# Sheet2.net
KiCad netlist of a schematic drawn in Altium Designer
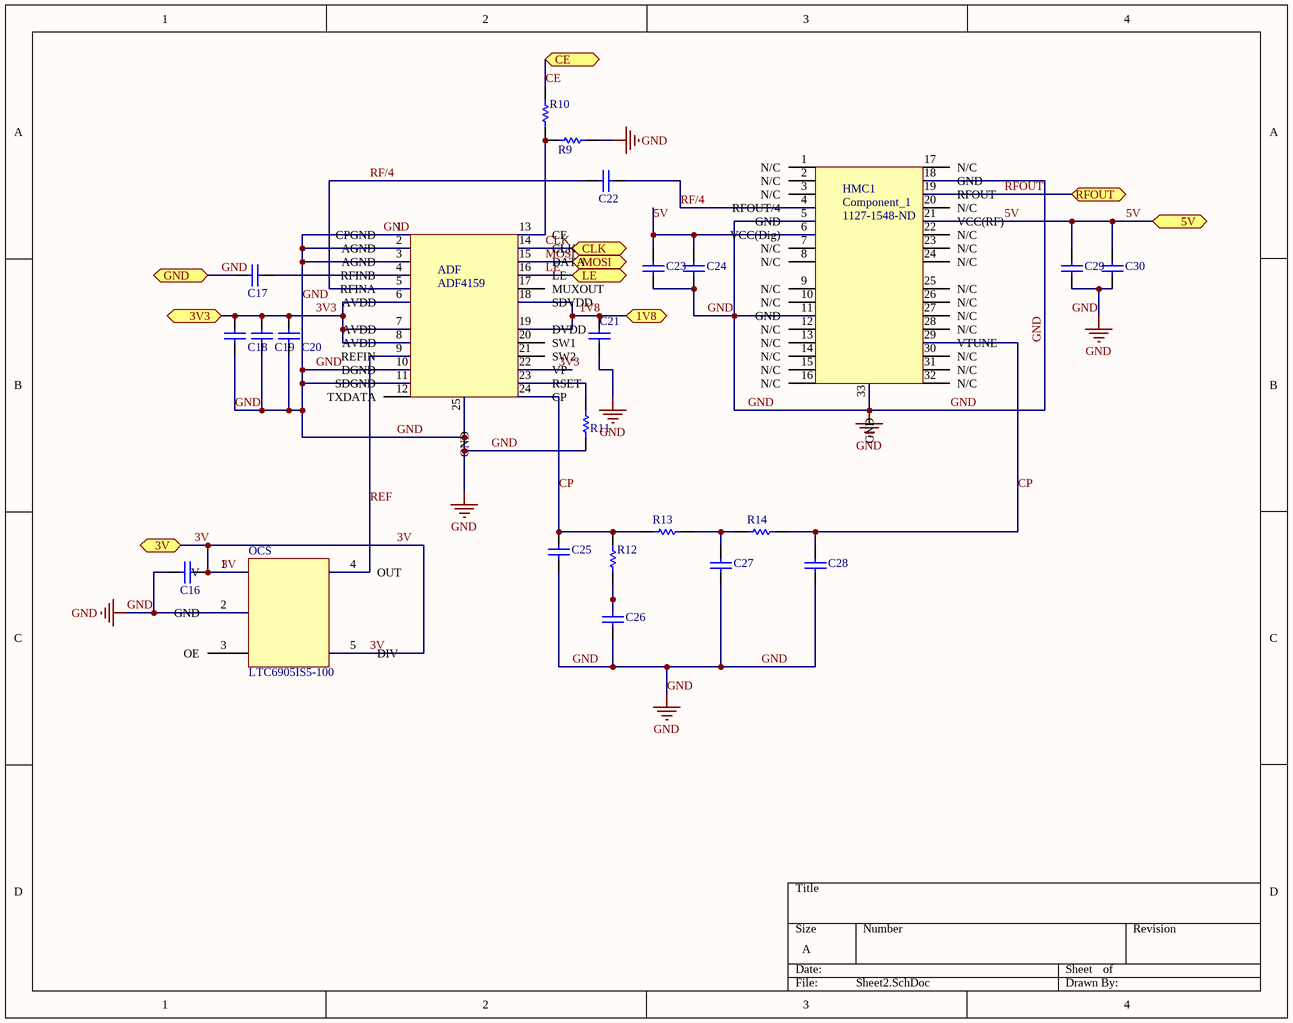
[diagram p0: Sheet2.SchDoc]

(export (version "E")
  (design (tool "Eeschema 10.0.6"))
  (components
    (comp (ref "ADF")
      (value "ADF4159")
      (footprint "QFN50P400X400X80_HS-25N")
      (libsource (lib "ADF4159") (part "ADF4159"))
    )
    (comp (ref "C16")
      (value "CAP 0.1uF 16V 0603(1608)")
      (footprint "CAPC0603(1608)100_L")
      (description "CAP 0.1uF 16V ±1% 0603 (1608 Metric) Thickness 1mm SMD")
      (fields (field (name "TOLERANCE") "Â±1%"))
      (libsource (lib "Altium Content Vault") (part "CMP-1035-01744-1"))
    )
    (comp (ref "C17")
      (value "CAP 100pF 16V 0603(1608)")
      (footprint "CAPC0603(1608)100_L")
      (description "CAP 100pF 16V ±1% 0603 (1608 Metric) Thickness 1mm SMD")
      (fields (field (name "TOLERANCE") "Â±1%"))
      (libsource (lib "Altium Content Vault") (part "CMP-1035-01744-1"))
    )
    (comp (ref "C18")
      (value "CAP 10uF 16V 0603(1608)")
      (footprint "CAPC0603(1608)100_L")
      (description "CAP 10uF 16V ±1% 0603 (1608 Metric) Thickness 1mm SMD")
      (fields (field (name "TOLERANCE") "Â±1%"))
      (libsource (lib "Altium Content Vault") (part "CMP-1035-01744-1"))
    )
    (comp (ref "C19")
      (value "CAP 10uF 16V 0603(1608)")
      (footprint "CAPC0603(1608)100_L")
      (description "CAP 10uF 16V ±1% 0603 (1608 Metric) Thickness 1mm SMD")
      (fields (field (name "TOLERANCE") "Â±1%"))
      (libsource (lib "Altium Content Vault") (part "CMP-1035-01744-1"))
    )
    (comp (ref "C20")
      (value "CAP 10uF 16V 0603(1608)")
      (footprint "CAPC0603(1608)100_L")
      (description "CAP 10uF 16V ±1% 0603 (1608 Metric) Thickness 1mm SMD")
      (fields (field (name "TOLERANCE") "Â±1%"))
      (libsource (lib "Altium Content Vault") (part "CMP-1035-01744-1"))
    )
    (comp (ref "C21")
      (value "CAP 10uF 16V 0603(1608)")
      (footprint "CAPC0603(1608)100_L")
      (description "CAP 10uF 16V ±1% 0603 (1608 Metric) Thickness 1mm SMD")
      (fields (field (name "TOLERANCE") "Â±1%"))
      (libsource (lib "Altium Content Vault") (part "CMP-1035-01744-1"))
    )
    (comp (ref "C22")
      (value "CAP 1000pF 16V 0603(1608)")
      (footprint "CAPC0603(1608)100_L")
      (description "CAP 1000pF 16V ±1% 0603 (1608 Metric) Thickness 1mm SMD")
      (fields (field (name "TOLERANCE") "Â±1%"))
      (libsource (lib "Altium Content Vault") (part "CMP-1035-01744-1"))
    )
    (comp (ref "C23")
      (value "CAP 2.2uF 16V 0603(1608)")
      (footprint "CAPC0603(1608)100_L")
      (description "CAP 2.2uF 16V ±1% 0603 (1608 Metric) Thickness 1mm SMD")
      (fields (field (name "TOLERANCE") "Â±1%"))
      (libsource (lib "Altium Content Vault") (part "CMP-1035-01744-1"))
    )
    (comp (ref "C24")
      (value "CAP 100pF 16V 0603(1608)")
      (footprint "CAPC0603(1608)100_L")
      (description "CAP 100pF 16V ±1% 0603 (1608 Metric) Thickness 1mm SMD")
      (fields (field (name "TOLERANCE") "Â±1%"))
      (libsource (lib "Altium Content Vault") (part "CMP-1035-01744-1"))
    )
    (comp (ref "C25")
      (value "CAP 360pF 16V 0603(1608)")
      (footprint "CAPC0603(1608)100_L")
      (description "CAP 390pF 16V ±1% 0603 (1608 Metric) Thickness 1mm SMD")
      (fields (field (name "TOLERANCE") "Â±1%"))
      (libsource (lib "Altium Content Vault") (part "CMP-1035-01744-1"))
    )
    (comp (ref "C26")
      (value "CAP 5.6nF 16V 0603(1608)")
      (footprint "CAPC0603(1608)100_L")
      (description "CAP 5.6nF 16V ±1% 0603 (1608 Metric) Thickness 1mm SMD")
      (fields (field (name "TOLERANCE") "Â±1%"))
      (libsource (lib "Altium Content Vault") (part "CMP-1035-01744-1"))
    )
    (comp (ref "C27")
      (value "CAP 270pF 16V 0603(1608)")
      (footprint "CAPC0603(1608)100_L")
      (description "CAP 270pF 16V ±1% 0603 (1608 Metric) Thickness 1mm SMD")
      (fields (field (name "TOLERANCE") "Â±1%"))
      (libsource (lib "Altium Content Vault") (part "CMP-1035-01744-1"))
    )
    (comp (ref "C28")
      (value "CAP 270pF 16V 0603(1608)")
      (footprint "CAPC0603(1608)100_L")
      (description "CAP 270pF 16V ±1% 0603 (1608 Metric) Thickness 1mm SMD")
      (fields (field (name "TOLERANCE") "Â±1%"))
      (libsource (lib "Altium Content Vault") (part "CMP-1035-01744-1"))
    )
    (comp (ref "C29")
      (value "CAP 2.2uF 16V 0603(1608)")
      (footprint "CAPC0603(1608)100_L")
      (description "CAP 2.2uF 16V ±1% 0603 (1608 Metric) Thickness 1mm SMD")
      (fields (field (name "TOLERANCE") "Â±1%"))
      (libsource (lib "Altium Content Vault") (part "CMP-1035-01744-1"))
    )
    (comp (ref "C30")
      (value "CAP 100pF 16V 0603(1608)")
      (footprint "CAPC0603(1608)100_L")
      (description "CAP 100pF 16V ±1% 0603 (1608 Metric) Thickness 1mm SMD")
      (fields (field (name "TOLERANCE") "Â±1%"))
      (libsource (lib "Altium Content Vault") (part "CMP-1035-01744-1"))
    )
    (comp (ref "HMC1")
      (value "Component_1")
      (footprint "QFN50P500X500X100_HS-33N")
      (description "HMC735 IC Schematic")
      (fields (field (name "SUPPLIER PART NUMBER 1") "1127-1548-ND"))
      (libsource (lib "HMC735") (part "Component_1"))
    )
    (comp (ref "OCS")
      (value "LTC6905IS5-100")
      (footprint "TSOP95P280X100-5N")
      (libsource (lib "LTC6905IS5-100") (part "LTC6905IS5-100"))
    )
    (comp (ref "R9")
      (value "120 1% 0603(1608)")
      (footprint "RESC0603(1608)_N")
      (description "120 0.1W 1% 0603 (1608 Metric)  SMD")
      (fields (field (name "POWER") "0.1 W") (field (name "TOLERANCE") "1 %"))
      (libsource (lib "Altium Content Vault") (part "CMP-1012-00736-1"))
    )
    (comp (ref "R10")
      (value "100 1% 0603(1608)")
      (footprint "RESC0603(1608)_N")
      (description "100 0.1W 1% 0603 (1608 Metric)  SMD")
      (fields (field (name "POWER") "0.1 W") (field (name "TOLERANCE") "1 %"))
      (libsource (lib "Altium Content Vault") (part "CMP-1012-00736-1"))
    )
    (comp (ref "R11")
      (value "5100 1% 0603(1608)")
      (footprint "RESC0603(1608)_N")
      (description "5100 0.1W 1% 0603 (1608 Metric)  SMD")
      (fields (field (name "POWER") "0.1 W") (field (name "TOLERANCE") "1 %"))
      (libsource (lib "Altium Content Vault") (part "CMP-1012-00736-1"))
    )
    (comp (ref "R12")
      (value "330 1% 0603(1608)")
      (footprint "RESC0603(1608)_N")
      (description "330 0.1W 1% 0603 (1608 Metric)  SMD")
      (fields (field (name "POWER") "0.1 W") (field (name "TOLERANCE") "1 %"))
      (libsource (lib "Altium Content Vault") (part "CMP-1012-00736-1"))
    )
    (comp (ref "R13")
      (value "180 1% 0603(1608)")
      (footprint "RESC0603(1608)_N")
      (description "180 0.1W 1% 0603 (1608 Metric)  SMD")
      (fields (field (name "POWER") "0.1 W") (field (name "TOLERANCE") "1 %"))
      (libsource (lib "Altium Content Vault") (part "CMP-1012-00736-1"))
    )
    (comp (ref "R14")
      (value "180 1% 0603(1608)")
      (footprint "RESC0603(1608)_N")
      (description "180 0.1W 1% 0603 (1608 Metric)  SMD")
      (fields (field (name "POWER") "0.1 W") (field (name "TOLERANCE") "1 %"))
      (libsource (lib "Altium Content Vault") (part "CMP-1012-00736-1"))
    )
  )
  (nets
    (net (code "1") (name "/1V8") (class "Default")
      (node (ref "ADF") (pin "18") (pinfunction "SDVDD_18") (pintype "passive"))
      (node (ref "ADF") (pin "19") (pinfunction "DVDD_19") (pintype "passive"))
      (node (ref "C21") (pin "1") (pinfunction "1_1") (pintype "passive"))
    )
    (net (code "2") (name "/3V") (class "Default")
      (node (ref "C16") (pin "1") (pinfunction "1_1") (pintype "passive"))
      (node (ref "OCS") (pin "1") (pinfunction "V_1") (pintype "passive"))
      (node (ref "OCS") (pin "5") (pinfunction "DIV_5") (pintype "passive"))
    )
    (net (code "3") (name "/3V3") (class "Default")
      (node (ref "ADF") (pin "22") (pinfunction "VP_22") (pintype "passive"))
      (node (ref "ADF") (pin "6") (pinfunction "AVDD_6") (pintype "passive"))
      (node (ref "ADF") (pin "7") (pinfunction "AVDD_7") (pintype "passive"))
      (node (ref "ADF") (pin "8") (pinfunction "AVDD_8") (pintype "passive"))
      (node (ref "C18") (pin "1") (pinfunction "1_1") (pintype "passive"))
      (node (ref "C19") (pin "1") (pinfunction "1_1") (pintype "passive"))
      (node (ref "C20") (pin "1") (pinfunction "1_1") (pintype "passive"))
    )
    (net (code "4") (name "/5V") (class "Default")
      (node (ref "C23") (pin "2") (pinfunction "2_2") (pintype "passive"))
      (node (ref "C24") (pin "2") (pinfunction "2_2") (pintype "passive"))
      (node (ref "C29") (pin "2") (pinfunction "2_2") (pintype "passive"))
      (node (ref "C30") (pin "2") (pinfunction "2_2") (pintype "passive"))
      (node (ref "HMC1") (pin "21") (pinfunction "VCC(RF)_21") (pintype "passive"))
      (node (ref "HMC1") (pin "6") (pinfunction "VCC(Dig)_6") (pintype "passive"))
    )
    (net (code "5") (name "/CE") (class "Default")
      (node (ref "R10") (pin "2") (pinfunction "2_2") (pintype "passive"))
    )
    (net (code "6") (name "/CLK") (class "Default")
      (node (ref "ADF") (pin "14") (pinfunction "CLK_14") (pintype "passive"))
    )
    (net (code "7") (name "/CP") (class "Default")
      (node (ref "ADF") (pin "24") (pinfunction "CP_24") (pintype "passive"))
      (node (ref "C25") (pin "1") (pinfunction "1_1") (pintype "passive"))
      (node (ref "C28") (pin "2") (pinfunction "2_2") (pintype "passive"))
      (node (ref "HMC1") (pin "29") (pinfunction "VTUNE_29") (pintype "passive"))
      (node (ref "R12") (pin "2") (pinfunction "2_2") (pintype "passive"))
      (node (ref "R13") (pin "1") (pinfunction "1_1") (pintype "passive"))
      (node (ref "R14") (pin "2") (pinfunction "2_2") (pintype "passive"))
    )
    (net (code "8") (name "/LE") (class "Default")
      (node (ref "ADF") (pin "16") (pinfunction "LE_16") (pintype "passive"))
    )
    (net (code "9") (name "/MOSI") (class "Default")
      (node (ref "ADF") (pin "15") (pinfunction "DATA_15") (pintype "passive"))
    )
    (net (code "10") (name "/REF") (class "Default")
      (node (ref "ADF") (pin "9") (pinfunction "REFIN_9") (pintype "passive"))
      (node (ref "OCS") (pin "4") (pinfunction "OUT_4") (pintype "passive"))
    )
    (net (code "11") (name "/RFOUT") (class "Default")
      (node (ref "HMC1") (pin "19") (pinfunction "RFOUT_19") (pintype "passive"))
    )
    (net (code "12") (name "/RF{slash}4") (class "Default")
      (node (ref "ADF") (pin "5") (pinfunction "RFINA_5") (pintype "passive"))
      (node (ref "C22") (pin "1") (pinfunction "1_1") (pintype "passive"))
      (node (ref "C22") (pin "2") (pinfunction "2_2") (pintype "passive"))
      (node (ref "HMC1") (pin "4") (pinfunction "RFOUT/4_4") (pintype "passive"))
    )
    (net (code "13") (name "GND") (class "Default")
      (node (ref "ADF") (pin "1") (pinfunction "CPGND_1") (pintype "passive"))
      (node (ref "ADF") (pin "10") (pinfunction "DGND_10") (pintype "passive"))
      (node (ref "ADF") (pin "11") (pinfunction "SDGND_11") (pintype "passive"))
      (node (ref "ADF") (pin "2") (pinfunction "AGND_2") (pintype "passive"))
      (node (ref "ADF") (pin "25") (pinfunction "GND_25") (pintype "passive"))
      (node (ref "ADF") (pin "3") (pinfunction "AGND_3") (pintype "passive"))
      (node (ref "C16") (pin "2") (pinfunction "2_2") (pintype "passive"))
      (node (ref "C17") (pin "2") (pinfunction "2_2") (pintype "passive"))
      (node (ref "C18") (pin "2") (pinfunction "2_2") (pintype "passive"))
      (node (ref "C19") (pin "2") (pinfunction "2_2") (pintype "passive"))
      (node (ref "C20") (pin "2") (pinfunction "2_2") (pintype "passive"))
      (node (ref "C21") (pin "2") (pinfunction "2_2") (pintype "passive"))
      (node (ref "C23") (pin "1") (pinfunction "1_1") (pintype "passive"))
      (node (ref "C24") (pin "1") (pinfunction "1_1") (pintype "passive"))
      (node (ref "C25") (pin "2") (pinfunction "2_2") (pintype "passive"))
      (node (ref "C26") (pin "1") (pinfunction "1_1") (pintype "passive"))
      (node (ref "C27") (pin "1") (pinfunction "1_1") (pintype "passive"))
      (node (ref "C28") (pin "1") (pinfunction "1_1") (pintype "passive"))
      (node (ref "C29") (pin "1") (pinfunction "1_1") (pintype "passive"))
      (node (ref "C30") (pin "1") (pinfunction "1_1") (pintype "passive"))
      (node (ref "HMC1") (pin "11") (pinfunction "GND_11") (pintype "passive"))
      (node (ref "HMC1") (pin "18") (pinfunction "GND_18") (pintype "passive"))
      (node (ref "HMC1") (pin "33") (pinfunction "GND_33") (pintype "passive"))
      (node (ref "HMC1") (pin "5") (pinfunction "GND_5") (pintype "passive"))
      (node (ref "OCS") (pin "2") (pinfunction "GND_2") (pintype "passive"))
      (node (ref "R11") (pin "2") (pinfunction "2_2") (pintype "passive"))
      (node (ref "R9") (pin "1") (pinfunction "1_1") (pintype "passive"))
    )
    (net (code "14") (name "Net-(ADF-CE)") (class "Default")
      (node (ref "ADF") (pin "13") (pinfunction "CE_13") (pintype "passive"))
      (node (ref "R10") (pin "1") (pinfunction "1_1") (pintype "passive"))
      (node (ref "R9") (pin "2") (pinfunction "2_2") (pintype "passive"))
    )
    (net (code "15") (name "Net-(ADF-RFINB)") (class "Default")
      (node (ref "ADF") (pin "4") (pinfunction "RFINB_4") (pintype "passive"))
      (node (ref "C17") (pin "1") (pinfunction "1_1") (pintype "passive"))
    )
    (net (code "16") (name "Net-(ADF-RSET)") (class "Default")
      (node (ref "ADF") (pin "23") (pinfunction "RSET_23") (pintype "passive"))
      (node (ref "R11") (pin "1") (pinfunction "1_1") (pintype "passive"))
    )
    (net (code "17") (name "Net-(C26-Pad2)") (class "Default")
      (node (ref "C26") (pin "2") (pinfunction "2_2") (pintype "passive"))
      (node (ref "R12") (pin "1") (pinfunction "1_1") (pintype "passive"))
    )
    (net (code "18") (name "Net-(C27-Pad2)") (class "Default")
      (node (ref "C27") (pin "2") (pinfunction "2_2") (pintype "passive"))
      (node (ref "R13") (pin "2") (pinfunction "2_2") (pintype "passive"))
      (node (ref "R14") (pin "1") (pinfunction "1_1") (pintype "passive"))
    )
    (net (code "19") (name "unconnected-(ADF-MUXOUT-Pad17)") (class "Default")
      (node (ref "ADF") (pin "17") (pinfunction "MUXOUT_17") (pintype "passive"))
    )
    (net (code "20") (name "unconnected-(ADF-SW1-Pad20)") (class "Default")
      (node (ref "ADF") (pin "20") (pinfunction "SW1_20") (pintype "passive"))
    )
    (net (code "21") (name "unconnected-(ADF-SW2-Pad21)") (class "Default")
      (node (ref "ADF") (pin "21") (pinfunction "SW2_21") (pintype "passive"))
    )
    (net (code "22") (name "unconnected-(ADF-TXDATA-Pad12)") (class "Default")
      (node (ref "ADF") (pin "12") (pinfunction "TXDATA_12") (pintype "passive"))
    )
    (net (code "23") (name "unconnected-(HMC1-N{slash}C-Pad1)") (class "Default")
      (node (ref "HMC1") (pin "1") (pinfunction "N/C_1") (pintype "passive"))
    )
    (net (code "24") (name "unconnected-(HMC1-N{slash}C-Pad2)") (class "Default")
      (node (ref "HMC1") (pin "2") (pinfunction "N/C_2") (pintype "passive"))
    )
    (net (code "25") (name "unconnected-(HMC1-N{slash}C-Pad3)") (class "Default")
      (node (ref "HMC1") (pin "3") (pinfunction "N/C_3") (pintype "passive"))
    )
    (net (code "26") (name "unconnected-(HMC1-N{slash}C-Pad7)") (class "Default")
      (node (ref "HMC1") (pin "7") (pinfunction "N/C_7") (pintype "passive"))
    )
    (net (code "27") (name "unconnected-(HMC1-N{slash}C-Pad8)") (class "Default")
      (node (ref "HMC1") (pin "8") (pinfunction "N/C_8") (pintype "passive"))
    )
    (net (code "28") (name "unconnected-(HMC1-N{slash}C-Pad9)") (class "Default")
      (node (ref "HMC1") (pin "9") (pinfunction "N/C_9") (pintype "passive"))
    )
    (net (code "29") (name "unconnected-(HMC1-N{slash}C-Pad10)") (class "Default")
      (node (ref "HMC1") (pin "10") (pinfunction "N/C_10") (pintype "passive"))
    )
    (net (code "30") (name "unconnected-(HMC1-N{slash}C-Pad12)") (class "Default")
      (node (ref "HMC1") (pin "12") (pinfunction "N/C_12") (pintype "passive"))
    )
    (net (code "31") (name "unconnected-(HMC1-N{slash}C-Pad13)") (class "Default")
      (node (ref "HMC1") (pin "13") (pinfunction "N/C_13") (pintype "passive"))
    )
    (net (code "32") (name "unconnected-(HMC1-N{slash}C-Pad14)") (class "Default")
      (node (ref "HMC1") (pin "14") (pinfunction "N/C_14") (pintype "passive"))
    )
    (net (code "33") (name "unconnected-(HMC1-N{slash}C-Pad15)") (class "Default")
      (node (ref "HMC1") (pin "15") (pinfunction "N/C_15") (pintype "passive"))
    )
    (net (code "34") (name "unconnected-(HMC1-N{slash}C-Pad16)") (class "Default")
      (node (ref "HMC1") (pin "16") (pinfunction "N/C_16") (pintype "passive"))
    )
    (net (code "35") (name "unconnected-(HMC1-N{slash}C-Pad17)") (class "Default")
      (node (ref "HMC1") (pin "17") (pinfunction "N/C_17") (pintype "passive"))
    )
    (net (code "36") (name "unconnected-(HMC1-N{slash}C-Pad20)") (class "Default")
      (node (ref "HMC1") (pin "20") (pinfunction "N/C_20") (pintype "passive"))
    )
    (net (code "37") (name "unconnected-(HMC1-N{slash}C-Pad22)") (class "Default")
      (node (ref "HMC1") (pin "22") (pinfunction "N/C_22") (pintype "passive"))
    )
    (net (code "38") (name "unconnected-(HMC1-N{slash}C-Pad23)") (class "Default")
      (node (ref "HMC1") (pin "23") (pinfunction "N/C_23") (pintype "passive"))
    )
    (net (code "39") (name "unconnected-(HMC1-N{slash}C-Pad24)") (class "Default")
      (node (ref "HMC1") (pin "24") (pinfunction "N/C_24") (pintype "passive"))
    )
    (net (code "40") (name "unconnected-(HMC1-N{slash}C-Pad25)") (class "Default")
      (node (ref "HMC1") (pin "25") (pinfunction "N/C_25") (pintype "passive"))
    )
    (net (code "41") (name "unconnected-(HMC1-N{slash}C-Pad26)") (class "Default")
      (node (ref "HMC1") (pin "26") (pinfunction "N/C_26") (pintype "passive"))
    )
    (net (code "42") (name "unconnected-(HMC1-N{slash}C-Pad27)") (class "Default")
      (node (ref "HMC1") (pin "27") (pinfunction "N/C_27") (pintype "passive"))
    )
    (net (code "43") (name "unconnected-(HMC1-N{slash}C-Pad28)") (class "Default")
      (node (ref "HMC1") (pin "28") (pinfunction "N/C_28") (pintype "passive"))
    )
    (net (code "44") (name "unconnected-(HMC1-N{slash}C-Pad30)") (class "Default")
      (node (ref "HMC1") (pin "30") (pinfunction "N/C_30") (pintype "passive"))
    )
    (net (code "45") (name "unconnected-(HMC1-N{slash}C-Pad31)") (class "Default")
      (node (ref "HMC1") (pin "31") (pinfunction "N/C_31") (pintype "passive"))
    )
    (net (code "46") (name "unconnected-(HMC1-N{slash}C-Pad32)") (class "Default")
      (node (ref "HMC1") (pin "32") (pinfunction "N/C_32") (pintype "passive"))
    )
    (net (code "47") (name "unconnected-(OCS-OE-Pad3)") (class "Default")
      (node (ref "OCS") (pin "3") (pinfunction "OE_3") (pintype "passive"))
    )
  )
)
